# Car.net
KiCad netlist of a schematic drawn in EAGLE
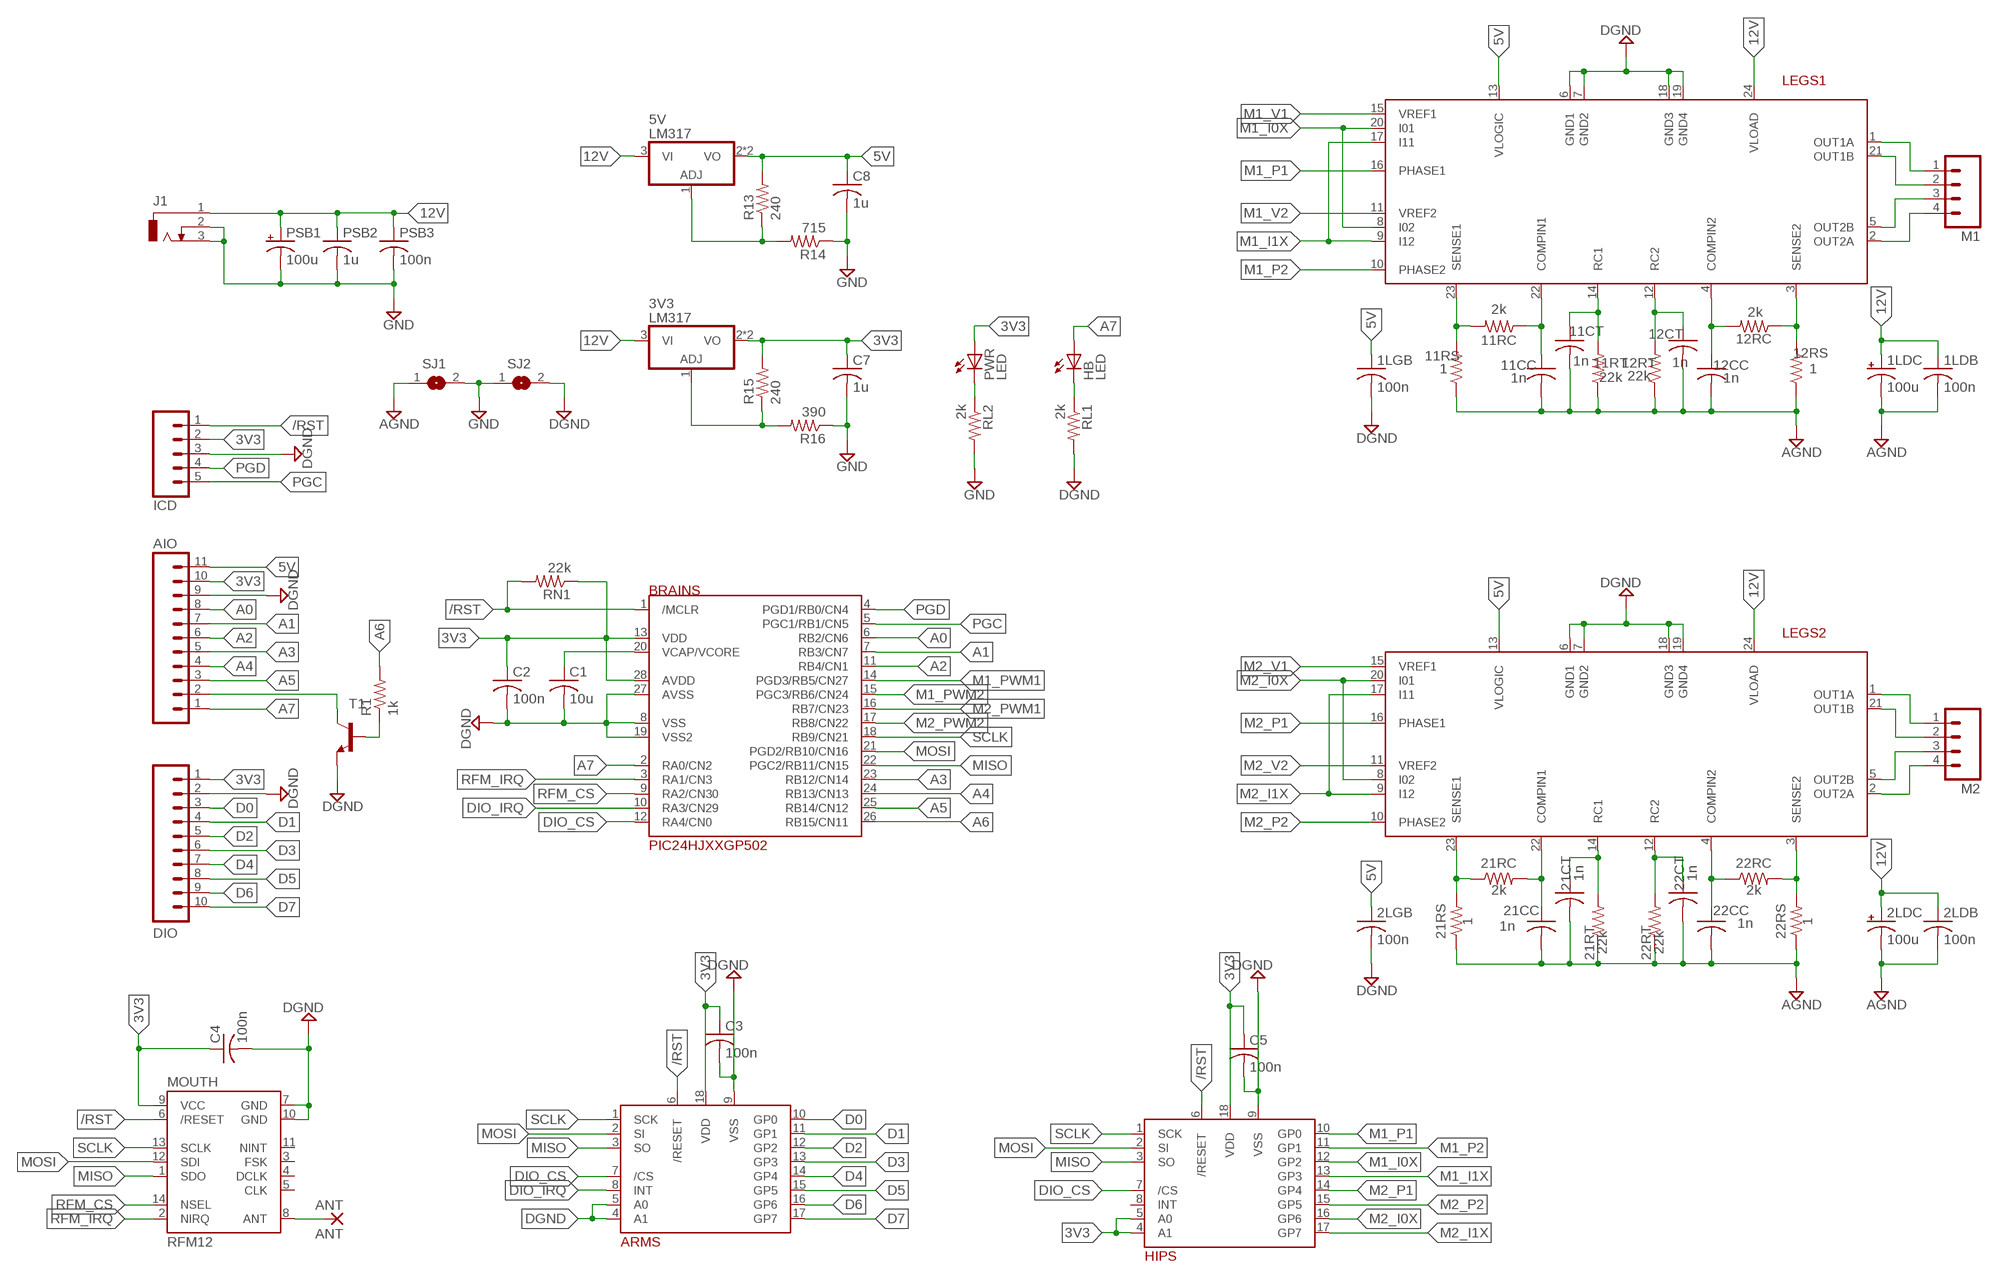
[diagram p0: schematic, sheet 1, part 1 of 2]
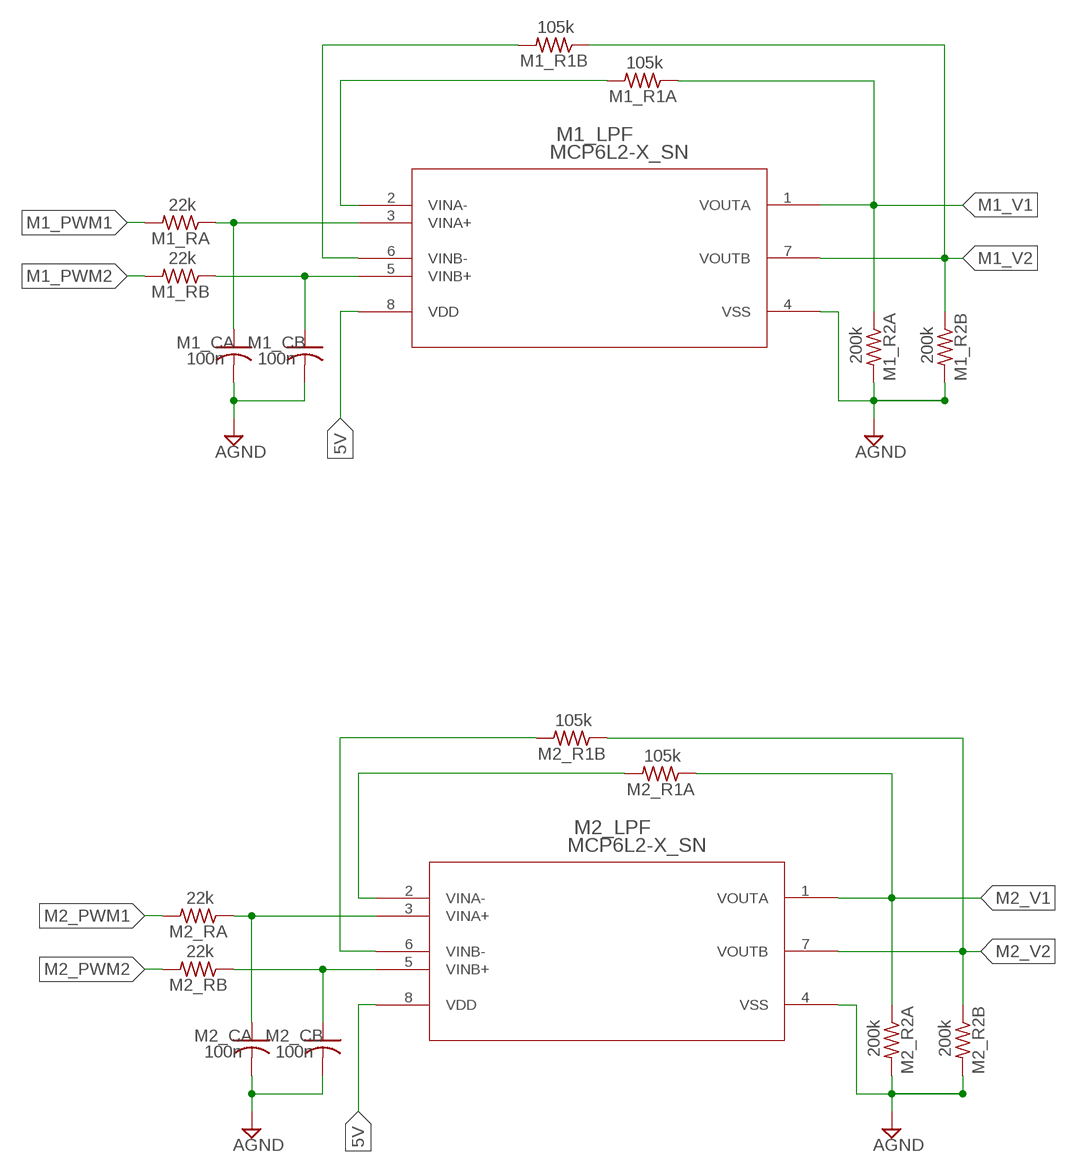
[diagram p1: schematic, sheet 1, part 2 of 2]

(export (version "E")
  (design (tool "Eeschema 10.0.6"))
  (components
    (comp (ref "1LDB")
      (value "100n")
      (footprint "eagle-import:C0805")
      (libsource (lib "eagle-import") (part "C-USC0805"))
    )
    (comp (ref "1LDC")
      (value "100u")
      (footprint "eagle-import:PANASONIC_C")
      (libsource (lib "eagle-import") (part "CAP_POLC"))
    )
    (comp (ref "1LGB")
      (value "100n")
      (footprint "eagle-import:C0805")
      (libsource (lib "eagle-import") (part "C-USC0805"))
    )
    (comp (ref "2LDB")
      (value "100n")
      (footprint "eagle-import:C0805")
      (libsource (lib "eagle-import") (part "C-USC0805"))
    )
    (comp (ref "2LDC")
      (value "100u")
      (footprint "eagle-import:PANASONIC_C")
      (libsource (lib "eagle-import") (part "CAP_POLC"))
    )
    (comp (ref "2LGB")
      (value "100n")
      (footprint "eagle-import:C0805")
      (libsource (lib "eagle-import") (part "C-USC0805"))
    )
    (comp (ref "3V3")
      (value "LM317")
      (footprint "eagle-import:SOT23")
      (libsource (lib "eagle-import") (part "LM317"))
    )
    (comp (ref "5V")
      (value "LM317")
      (footprint "eagle-import:SOT23")
      (libsource (lib "eagle-import") (part "LM317"))
    )
    (comp (ref "11CC")
      (value "1n")
      (footprint "eagle-import:C0805")
      (libsource (lib "eagle-import") (part "C-USC0805"))
    )
    (comp (ref "11CT")
      (value "1n")
      (footprint "eagle-import:C0805")
      (libsource (lib "eagle-import") (part "C-USC0805"))
    )
    (comp (ref "11RC")
      (value "2k")
      (footprint "eagle-import:R0805")
      (libsource (lib "eagle-import") (part "R-US_R0805"))
    )
    (comp (ref "11RS")
      (value "1")
      (footprint "eagle-import:R2512")
      (libsource (lib "eagle-import") (part "resistor_R-US_R2512"))
    )
    (comp (ref "11RT")
      (value "22k")
      (footprint "eagle-import:R0805")
      (libsource (lib "eagle-import") (part "R-US_R0805"))
    )
    (comp (ref "12CC")
      (value "1n")
      (footprint "eagle-import:C0805")
      (libsource (lib "eagle-import") (part "C-USC0805"))
    )
    (comp (ref "12CT")
      (value "1n")
      (footprint "eagle-import:C0805")
      (libsource (lib "eagle-import") (part "C-USC0805"))
    )
    (comp (ref "12RC")
      (value "2k")
      (footprint "eagle-import:R0805")
      (libsource (lib "eagle-import") (part "R-US_R0805"))
    )
    (comp (ref "12RS")
      (value "1")
      (footprint "eagle-import:R2512")
      (libsource (lib "eagle-import") (part "resistor_R-US_R2512"))
    )
    (comp (ref "12RT")
      (value "22k")
      (footprint "eagle-import:R0805")
      (libsource (lib "eagle-import") (part "R-US_R0805"))
    )
    (comp (ref "21CC")
      (value "1n")
      (footprint "eagle-import:C0805")
      (libsource (lib "eagle-import") (part "C-USC0805"))
    )
    (comp (ref "21CT")
      (value "1n")
      (footprint "eagle-import:C0805")
      (libsource (lib "eagle-import") (part "C-USC0805"))
    )
    (comp (ref "21RC")
      (value "2k")
      (footprint "eagle-import:R0805")
      (libsource (lib "eagle-import") (part "R-US_R0805"))
    )
    (comp (ref "21RS")
      (value "1")
      (footprint "eagle-import:R2512")
      (libsource (lib "eagle-import") (part "resistor_R-US_R2512"))
    )
    (comp (ref "21RT")
      (value "22k")
      (footprint "eagle-import:R0805")
      (libsource (lib "eagle-import") (part "R-US_R0805"))
    )
    (comp (ref "22CC")
      (value "1n")
      (footprint "eagle-import:C0805")
      (libsource (lib "eagle-import") (part "C-USC0805"))
    )
    (comp (ref "22CT")
      (value "1n")
      (footprint "eagle-import:C0805")
      (libsource (lib "eagle-import") (part "C-USC0805"))
    )
    (comp (ref "22RC")
      (value "2k")
      (footprint "eagle-import:R0805")
      (libsource (lib "eagle-import") (part "R-US_R0805"))
    )
    (comp (ref "22RS")
      (value "1")
      (footprint "eagle-import:R2512")
      (libsource (lib "eagle-import") (part "resistor_R-US_R2512"))
    )
    (comp (ref "22RT")
      (value "22k")
      (footprint "eagle-import:R0805")
      (libsource (lib "eagle-import") (part "R-US_R0805"))
    )
    (comp (ref "AIO")
      (value "M11LOCK")
      (footprint "eagle-import:1X11_LOCK")
      (libsource (lib "eagle-import") (part "M11LOCK"))
    )
    (comp (ref "ANT")
      (value "ANT")
      (footprint "eagle-import:2,15_1,0")
      (libsource (lib "eagle-import") (part "2,15/1,0"))
    )
    (comp (ref "ARMS")
      (value "MCP23S08")
      (footprint "eagle-import:SO-18W")
      (libsource (lib "eagle-import") (part "MCP23S08"))
    )
    (comp (ref "BRAINS")
      (value "PIC24HJXXGP502")
      (footprint "eagle-import:SO28W")
      (libsource (lib "eagle-import") (part "PIC24HJXXGP502"))
    )
    (comp (ref "C1")
      (value "10u")
      (footprint "eagle-import:C1206")
      (libsource (lib "eagle-import") (part "C-USC1206"))
    )
    (comp (ref "C2")
      (value "100n")
      (footprint "eagle-import:C0805")
      (libsource (lib "eagle-import") (part "C-USC0805"))
    )
    (comp (ref "C3")
      (value "100n")
      (footprint "eagle-import:C0805")
      (libsource (lib "eagle-import") (part "C-USC0805"))
    )
    (comp (ref "C4")
      (value "100n")
      (footprint "eagle-import:C0805")
      (libsource (lib "eagle-import") (part "C-USC0805"))
    )
    (comp (ref "C5")
      (value "100n")
      (footprint "eagle-import:C0805")
      (libsource (lib "eagle-import") (part "C-USC0805"))
    )
    (comp (ref "C7")
      (value "1u")
      (footprint "eagle-import:C1206")
      (libsource (lib "eagle-import") (part "C-USC1206"))
    )
    (comp (ref "C8")
      (value "1u")
      (footprint "eagle-import:C1206")
      (libsource (lib "eagle-import") (part "C-USC1206"))
    )
    (comp (ref "DIO")
      (value "M10LOCK")
      (footprint "eagle-import:1X10_LOCK")
      (libsource (lib "eagle-import") (part "M10LOCK"))
    )
    (comp (ref "HB")
      (value "LED")
      (footprint "eagle-import:CHIP-LED0805")
      (libsource (lib "eagle-import") (part "LEDCHIP-LED0805"))
    )
    (comp (ref "HIPS")
      (value "MCP23S08")
      (footprint "eagle-import:SO-18W")
      (libsource (lib "eagle-import") (part "MCP23S08"))
    )
    (comp (ref "ICD")
      (value "M05LOCK")
      (footprint "eagle-import:1X05_LOCK")
      (libsource (lib "eagle-import") (part "M05LOCK"))
    )
    (comp (ref "J1")
      (value "DCJ0303")
      (footprint "eagle-import:DCJ0303")
      (libsource (lib "eagle-import") (part "DCJ0303"))
    )
    (comp (ref "LEGS1")
      (value "MTS62C19A")
      (footprint "eagle-import:SOP24L")
      (libsource (lib "eagle-import") (part "MTS62C19A"))
    )
    (comp (ref "LEGS2")
      (value "MTS62C19A")
      (footprint "eagle-import:SOP24L")
      (libsource (lib "eagle-import") (part "MTS62C19A"))
    )
    (comp (ref "M1")
      (value "M04LOCK_LONGPADS")
      (footprint "eagle-import:1X04_LOCK_LONGPADS")
      (libsource (lib "eagle-import") (part "M04LOCK_LONGPADS"))
    )
    (comp (ref "M1_CA")
      (value "100n")
      (footprint "eagle-import:C0805")
      (libsource (lib "eagle-import") (part "C-USC0805"))
    )
    (comp (ref "M1_CB")
      (value "100n")
      (footprint "eagle-import:C0805")
      (libsource (lib "eagle-import") (part "C-USC0805"))
    )
    (comp (ref "M1_LPF")
      (value "MCP6L2-X_SN")
      (footprint "eagle-import:SOIC8-N_MC")
      (libsource (lib "eagle-import") (part "MCP6L2-X_SN"))
    )
    (comp (ref "M1_R1A")
      (value "105k")
      (footprint "eagle-import:R0805")
      (libsource (lib "eagle-import") (part "R-US_R0805"))
    )
    (comp (ref "M1_R1B")
      (value "105k")
      (footprint "eagle-import:R0805")
      (libsource (lib "eagle-import") (part "R-US_R0805"))
    )
    (comp (ref "M1_R2A")
      (value "200k")
      (footprint "eagle-import:R0805")
      (libsource (lib "eagle-import") (part "R-US_R0805"))
    )
    (comp (ref "M1_R2B")
      (value "200k")
      (footprint "eagle-import:R0805")
      (libsource (lib "eagle-import") (part "R-US_R0805"))
    )
    (comp (ref "M1_RA")
      (value "22k")
      (footprint "eagle-import:R0805")
      (libsource (lib "eagle-import") (part "R-US_R0805"))
    )
    (comp (ref "M1_RB")
      (value "22k")
      (footprint "eagle-import:R0805")
      (libsource (lib "eagle-import") (part "R-US_R0805"))
    )
    (comp (ref "M2")
      (value "M04LOCK_LONGPADS")
      (footprint "eagle-import:1X04_LOCK_LONGPADS")
      (libsource (lib "eagle-import") (part "M04LOCK_LONGPADS"))
    )
    (comp (ref "M2_CA")
      (value "100n")
      (footprint "eagle-import:C0805")
      (libsource (lib "eagle-import") (part "C-USC0805"))
    )
    (comp (ref "M2_CB")
      (value "100n")
      (footprint "eagle-import:C0805")
      (libsource (lib "eagle-import") (part "C-USC0805"))
    )
    (comp (ref "M2_LPF")
      (value "MCP6L2-X_SN")
      (footprint "eagle-import:SOIC8-N_MC")
      (libsource (lib "eagle-import") (part "MCP6L2-X_SN"))
    )
    (comp (ref "M2_R1A")
      (value "105k")
      (footprint "eagle-import:R0805")
      (libsource (lib "eagle-import") (part "R-US_R0805"))
    )
    (comp (ref "M2_R1B")
      (value "105k")
      (footprint "eagle-import:R0805")
      (libsource (lib "eagle-import") (part "R-US_R0805"))
    )
    (comp (ref "M2_R2A")
      (value "200k")
      (footprint "eagle-import:R0805")
      (libsource (lib "eagle-import") (part "R-US_R0805"))
    )
    (comp (ref "M2_R2B")
      (value "200k")
      (footprint "eagle-import:R0805")
      (libsource (lib "eagle-import") (part "R-US_R0805"))
    )
    (comp (ref "M2_RA")
      (value "22k")
      (footprint "eagle-import:R0805")
      (libsource (lib "eagle-import") (part "R-US_R0805"))
    )
    (comp (ref "M2_RB")
      (value "22k")
      (footprint "eagle-import:R0805")
      (libsource (lib "eagle-import") (part "R-US_R0805"))
    )
    (comp (ref "MOUTH")
      (value "RFM12")
      (footprint "eagle-import:RFM12-XXX-S2")
      (libsource (lib "eagle-import") (part "RFM12"))
    )
    (comp (ref "PSB1")
      (value "100u")
      (footprint "eagle-import:PANASONIC_C")
      (libsource (lib "eagle-import") (part "CAP_POLC"))
    )
    (comp (ref "PSB2")
      (value "1u")
      (footprint "eagle-import:C1206")
      (libsource (lib "eagle-import") (part "C-USC1206"))
    )
    (comp (ref "PSB3")
      (value "100n")
      (footprint "eagle-import:C0805")
      (libsource (lib "eagle-import") (part "C-USC0805"))
    )
    (comp (ref "PWR")
      (value "LED")
      (footprint "eagle-import:CHIP-LED0805")
      (libsource (lib "eagle-import") (part "LEDCHIP-LED0805"))
    )
    (comp (ref "R1")
      (value "1k")
      (footprint "eagle-import:R0805")
      (libsource (lib "eagle-import") (part "R-US_R0805"))
    )
    (comp (ref "R13")
      (value "240")
      (footprint "eagle-import:R0805")
      (libsource (lib "eagle-import") (part "R-US_R0805"))
    )
    (comp (ref "R14")
      (value "715")
      (footprint "eagle-import:R0805")
      (libsource (lib "eagle-import") (part "R-US_R0805"))
    )
    (comp (ref "R15")
      (value "240")
      (footprint "eagle-import:R0805")
      (libsource (lib "eagle-import") (part "R-US_R0805"))
    )
    (comp (ref "R16")
      (value "390")
      (footprint "eagle-import:R0805")
      (libsource (lib "eagle-import") (part "R-US_R0805"))
    )
    (comp (ref "RL1")
      (value "2k")
      (footprint "eagle-import:R0805")
      (libsource (lib "eagle-import") (part "R-US_R0805"))
    )
    (comp (ref "RL2")
      (value "2k")
      (footprint "eagle-import:R0805")
      (libsource (lib "eagle-import") (part "R-US_R0805"))
    )
    (comp (ref "RN1")
      (value "22k")
      (footprint "eagle-import:R0805")
      (libsource (lib "eagle-import") (part "R-US_R0805"))
    )
    (comp (ref "SJ1") (value "SJ") (footprint "eagle-import:SJ") (libsource (lib "eagle-import") (part "SJ")))
    (comp (ref "SJ2") (value "SJ") (footprint "eagle-import:SJ") (libsource (lib "eagle-import") (part "SJ")))
    (comp (ref "T1")
      (value "BC817-16-NPN-SOT23-BEC")
      (footprint "eagle-import:SOT23-BEC")
      (libsource (lib "eagle-import") (part "-NPN-SOT23-BECBC817-16"))
    )
  )
  (nets
    (net (code "1") (name "3V3") (class "Default")
      (node (ref "3V3") (pin "2") (pinfunction "VO_2") (pintype "passive"))
      (node (ref "3V3") (pin "4") (pinfunction "VO_4") (pintype "passive"))
      (node (ref "AIO") (pin "10") (pinfunction "10_10") (pintype "passive"))
      (node (ref "ARMS") (pin "18") (pinfunction "VDD_18") (pintype "bidirectional"))
      (node (ref "BRAINS") (pin "13") (pinfunction "VDD_13") (pintype "bidirectional"))
      (node (ref "BRAINS") (pin "28") (pinfunction "AVDD_28") (pintype "bidirectional"))
      (node (ref "C2") (pin "1") (pinfunction "1_1") (pintype "passive"))
      (node (ref "C3") (pin "1") (pinfunction "1_1") (pintype "passive"))
      (node (ref "C4") (pin "1") (pinfunction "1_1") (pintype "passive"))
      (node (ref "C5") (pin "1") (pinfunction "1_1") (pintype "passive"))
      (node (ref "C7") (pin "1") (pinfunction "1_1") (pintype "passive"))
      (node (ref "DIO") (pin "1") (pinfunction "1_1") (pintype "passive"))
      (node (ref "HIPS") (pin "18") (pinfunction "VDD_18") (pintype "bidirectional"))
      (node (ref "HIPS") (pin "4") (pinfunction "A1_4") (pintype "bidirectional"))
      (node (ref "HIPS") (pin "5") (pinfunction "A0_5") (pintype "bidirectional"))
      (node (ref "ICD") (pin "2") (pinfunction "2_2") (pintype "passive"))
      (node (ref "MOUTH") (pin "9") (pinfunction "VCC_9") (pintype "bidirectional"))
      (node (ref "PWR") (pin "A") (pinfunction "A_A") (pintype "passive"))
      (node (ref "R15") (pin "2") (pinfunction "2_2") (pintype "passive"))
      (node (ref "RN1") (pin "1") (pinfunction "1_1") (pintype "passive"))
    )
    (net (code "2") (name "5V") (class "Default")
      (node (ref "1LGB") (pin "1") (pinfunction "1_1") (pintype "passive"))
      (node (ref "2LGB") (pin "1") (pinfunction "1_1") (pintype "passive"))
      (node (ref "5V") (pin "2") (pinfunction "VO_2") (pintype "passive"))
      (node (ref "5V") (pin "4") (pinfunction "VO_4") (pintype "passive"))
      (node (ref "AIO") (pin "11") (pinfunction "11_11") (pintype "passive"))
      (node (ref "C8") (pin "1") (pinfunction "1_1") (pintype "passive"))
      (node (ref "LEGS1") (pin "13") (pinfunction "VLOGIC_13") (pintype "bidirectional"))
      (node (ref "LEGS2") (pin "13") (pinfunction "VLOGIC_13") (pintype "bidirectional"))
      (node (ref "M1_LPF") (pin "8") (pinfunction "VDD_8") (pintype "power_in"))
      (node (ref "M2_LPF") (pin "8") (pinfunction "VDD_8") (pintype "power_in"))
      (node (ref "R13") (pin "2") (pinfunction "2_2") (pintype "passive"))
    )
    (net (code "3") (name "12V") (class "Default")
      (node (ref "1LDB") (pin "1") (pinfunction "1_1") (pintype "passive"))
      (node (ref "1LDC") (pin "+") (pinfunction "+_+") (pintype "passive"))
      (node (ref "2LDB") (pin "1") (pinfunction "1_1") (pintype "passive"))
      (node (ref "2LDC") (pin "+") (pinfunction "+_+") (pintype "passive"))
      (node (ref "3V3") (pin "3") (pinfunction "VI_3") (pintype "input"))
      (node (ref "5V") (pin "3") (pinfunction "VI_3") (pintype "input"))
      (node (ref "J1") (pin "1") (pinfunction "1_1") (pintype "passive"))
      (node (ref "LEGS1") (pin "24") (pinfunction "VLOAD_24") (pintype "bidirectional"))
      (node (ref "LEGS2") (pin "24") (pinfunction "VLOAD_24") (pintype "bidirectional"))
      (node (ref "PSB1") (pin "+") (pinfunction "+_+") (pintype "passive"))
      (node (ref "PSB2") (pin "1") (pinfunction "1_1") (pintype "passive"))
      (node (ref "PSB3") (pin "1") (pinfunction "1_1") (pintype "passive"))
    )
    (net (code "4") (name "A0") (class "Default")
      (node (ref "AIO") (pin "8") (pinfunction "8_8") (pintype "passive"))
      (node (ref "BRAINS") (pin "6") (pinfunction "RB2/CN6_6") (pintype "bidirectional"))
    )
    (net (code "5") (name "A1") (class "Default")
      (node (ref "AIO") (pin "7") (pinfunction "7_7") (pintype "passive"))
      (node (ref "BRAINS") (pin "7") (pinfunction "RB3/CN7_7") (pintype "bidirectional"))
    )
    (net (code "6") (name "A2") (class "Default")
      (node (ref "AIO") (pin "6") (pinfunction "6_6") (pintype "passive"))
      (node (ref "BRAINS") (pin "11") (pinfunction "RB4/CN1_11") (pintype "bidirectional"))
    )
    (net (code "7") (name "A3") (class "Default")
      (node (ref "AIO") (pin "5") (pinfunction "5_5") (pintype "passive"))
      (node (ref "BRAINS") (pin "23") (pinfunction "RB12/CN14_23") (pintype "bidirectional"))
    )
    (net (code "8") (name "A4") (class "Default")
      (node (ref "AIO") (pin "4") (pinfunction "4_4") (pintype "passive"))
      (node (ref "BRAINS") (pin "24") (pinfunction "RB13/CN13_24") (pintype "bidirectional"))
    )
    (net (code "9") (name "A5") (class "Default")
      (node (ref "AIO") (pin "3") (pinfunction "3_3") (pintype "passive"))
      (node (ref "BRAINS") (pin "25") (pinfunction "RB14/CN12_25") (pintype "bidirectional"))
    )
    (net (code "10") (name "A6") (class "Default")
      (node (ref "BRAINS") (pin "26") (pinfunction "RB15/CN11_26") (pintype "bidirectional"))
      (node (ref "R1") (pin "2") (pinfunction "2_2") (pintype "passive"))
    )
    (net (code "11") (name "A7") (class "Default")
      (node (ref "AIO") (pin "1") (pinfunction "1_1") (pintype "passive"))
      (node (ref "BRAINS") (pin "2") (pinfunction "RA0/CN2_2") (pintype "bidirectional"))
      (node (ref "HB") (pin "A") (pinfunction "A_A") (pintype "passive"))
    )
    (net (code "12") (name "AGND") (class "Default")
      (node (ref "11CC") (pin "2") (pinfunction "2_2") (pintype "passive"))
      (node (ref "11CT") (pin "2") (pinfunction "2_2") (pintype "passive"))
      (node (ref "11RS") (pin "1") (pinfunction "1_1") (pintype "passive"))
      (node (ref "11RT") (pin "1") (pinfunction "1_1") (pintype "passive"))
      (node (ref "12CC") (pin "2") (pinfunction "2_2") (pintype "passive"))
      (node (ref "12CT") (pin "2") (pinfunction "2_2") (pintype "passive"))
      (node (ref "12RS") (pin "1") (pinfunction "1_1") (pintype "passive"))
      (node (ref "12RT") (pin "1") (pinfunction "1_1") (pintype "passive"))
      (node (ref "1LDB") (pin "2") (pinfunction "2_2") (pintype "passive"))
      (node (ref "1LDC") (pin "-") (pinfunction "-_-") (pintype "passive"))
      (node (ref "21CC") (pin "2") (pinfunction "2_2") (pintype "passive"))
      (node (ref "21CT") (pin "2") (pinfunction "2_2") (pintype "passive"))
      (node (ref "21RS") (pin "1") (pinfunction "1_1") (pintype "passive"))
      (node (ref "21RT") (pin "1") (pinfunction "1_1") (pintype "passive"))
      (node (ref "22CC") (pin "2") (pinfunction "2_2") (pintype "passive"))
      (node (ref "22CT") (pin "2") (pinfunction "2_2") (pintype "passive"))
      (node (ref "22RS") (pin "1") (pinfunction "1_1") (pintype "passive"))
      (node (ref "22RT") (pin "1") (pinfunction "1_1") (pintype "passive"))
      (node (ref "2LDB") (pin "2") (pinfunction "2_2") (pintype "passive"))
      (node (ref "2LDC") (pin "-") (pinfunction "-_-") (pintype "passive"))
      (node (ref "M1_CA") (pin "2") (pinfunction "2_2") (pintype "passive"))
      (node (ref "M1_CB") (pin "2") (pinfunction "2_2") (pintype "passive"))
      (node (ref "M1_LPF") (pin "4") (pinfunction "VSS_4") (pintype "power_in"))
      (node (ref "M1_R2A") (pin "2") (pinfunction "2_2") (pintype "passive"))
      (node (ref "M1_R2B") (pin "2") (pinfunction "2_2") (pintype "passive"))
      (node (ref "M2_CA") (pin "2") (pinfunction "2_2") (pintype "passive"))
      (node (ref "M2_CB") (pin "2") (pinfunction "2_2") (pintype "passive"))
      (node (ref "M2_LPF") (pin "4") (pinfunction "VSS_4") (pintype "power_in"))
      (node (ref "M2_R2A") (pin "2") (pinfunction "2_2") (pintype "passive"))
      (node (ref "M2_R2B") (pin "2") (pinfunction "2_2") (pintype "passive"))
      (node (ref "SJ1") (pin "1") (pinfunction "1_1") (pintype "passive"))
    )
    (net (code "13") (name "D0") (class "Default")
      (node (ref "ARMS") (pin "10") (pinfunction "GP0_10") (pintype "bidirectional"))
      (node (ref "DIO") (pin "3") (pinfunction "3_3") (pintype "passive"))
    )
    (net (code "14") (name "D1") (class "Default")
      (node (ref "ARMS") (pin "11") (pinfunction "GP1_11") (pintype "bidirectional"))
      (node (ref "DIO") (pin "4") (pinfunction "4_4") (pintype "passive"))
    )
    (net (code "15") (name "D2") (class "Default")
      (node (ref "ARMS") (pin "12") (pinfunction "GP2_12") (pintype "bidirectional"))
      (node (ref "DIO") (pin "5") (pinfunction "5_5") (pintype "passive"))
    )
    (net (code "16") (name "D3") (class "Default")
      (node (ref "ARMS") (pin "13") (pinfunction "GP3_13") (pintype "bidirectional"))
      (node (ref "DIO") (pin "6") (pinfunction "6_6") (pintype "passive"))
    )
    (net (code "17") (name "D4") (class "Default")
      (node (ref "ARMS") (pin "14") (pinfunction "GP4_14") (pintype "bidirectional"))
      (node (ref "DIO") (pin "7") (pinfunction "7_7") (pintype "passive"))
    )
    (net (code "18") (name "D5") (class "Default")
      (node (ref "ARMS") (pin "15") (pinfunction "GP5_15") (pintype "bidirectional"))
      (node (ref "DIO") (pin "8") (pinfunction "8_8") (pintype "passive"))
    )
    (net (code "19") (name "D6") (class "Default")
      (node (ref "ARMS") (pin "16") (pinfunction "GP6_16") (pintype "bidirectional"))
      (node (ref "DIO") (pin "9") (pinfunction "9_9") (pintype "passive"))
    )
    (net (code "20") (name "D7") (class "Default")
      (node (ref "ARMS") (pin "17") (pinfunction "GP7_17") (pintype "bidirectional"))
      (node (ref "DIO") (pin "10") (pinfunction "10_10") (pintype "passive"))
    )
    (net (code "21") (name "DGND") (class "Default")
      (node (ref "1LGB") (pin "2") (pinfunction "2_2") (pintype "passive"))
      (node (ref "2LGB") (pin "2") (pinfunction "2_2") (pintype "passive"))
      (node (ref "AIO") (pin "9") (pinfunction "9_9") (pintype "passive"))
      (node (ref "ARMS") (pin "4") (pinfunction "A1_4") (pintype "bidirectional"))
      (node (ref "ARMS") (pin "5") (pinfunction "A0_5") (pintype "bidirectional"))
      (node (ref "ARMS") (pin "9") (pinfunction "VSS_9") (pintype "bidirectional"))
      (node (ref "BRAINS") (pin "19") (pinfunction "VSS2_19") (pintype "bidirectional"))
      (node (ref "BRAINS") (pin "27") (pinfunction "AVSS_27") (pintype "bidirectional"))
      (node (ref "BRAINS") (pin "8") (pinfunction "VSS_8") (pintype "bidirectional"))
      (node (ref "C1") (pin "2") (pinfunction "2_2") (pintype "passive"))
      (node (ref "C2") (pin "2") (pinfunction "2_2") (pintype "passive"))
      (node (ref "C3") (pin "2") (pinfunction "2_2") (pintype "passive"))
      (node (ref "C4") (pin "2") (pinfunction "2_2") (pintype "passive"))
      (node (ref "C5") (pin "2") (pinfunction "2_2") (pintype "passive"))
      (node (ref "DIO") (pin "2") (pinfunction "2_2") (pintype "passive"))
      (node (ref "HIPS") (pin "9") (pinfunction "VSS_9") (pintype "bidirectional"))
      (node (ref "ICD") (pin "3") (pinfunction "3_3") (pintype "passive"))
      (node (ref "LEGS1") (pin "18") (pinfunction "GND3_18") (pintype "bidirectional"))
      (node (ref "LEGS1") (pin "19") (pinfunction "GND4_19") (pintype "bidirectional"))
      (node (ref "LEGS1") (pin "6") (pinfunction "GND1_6") (pintype "bidirectional"))
      (node (ref "LEGS1") (pin "7") (pinfunction "GND2_7") (pintype "bidirectional"))
      (node (ref "LEGS2") (pin "18") (pinfunction "GND3_18") (pintype "bidirectional"))
      (node (ref "LEGS2") (pin "19") (pinfunction "GND4_19") (pintype "bidirectional"))
      (node (ref "LEGS2") (pin "6") (pinfunction "GND1_6") (pintype "bidirectional"))
      (node (ref "LEGS2") (pin "7") (pinfunction "GND2_7") (pintype "bidirectional"))
      (node (ref "MOUTH") (pin "10") (pinfunction "GND_10") (pintype "bidirectional"))
      (node (ref "MOUTH") (pin "7") (pinfunction "GND_7") (pintype "bidirectional"))
      (node (ref "RL1") (pin "2") (pinfunction "2_2") (pintype "passive"))
      (node (ref "SJ2") (pin "2") (pinfunction "2_2") (pintype "passive"))
      (node (ref "T1") (pin "E") (pinfunction "E_E") (pintype "passive"))
    )
    (net (code "22") (name "DIO_CS") (class "Default")
      (node (ref "ARMS") (pin "7") (pinfunction "/CS_7") (pintype "bidirectional"))
      (node (ref "BRAINS") (pin "12") (pinfunction "RA4/CN0_12") (pintype "bidirectional"))
      (node (ref "HIPS") (pin "7") (pinfunction "/CS_7") (pintype "bidirectional"))
    )
    (net (code "23") (name "DIO_IRQ") (class "Default")
      (node (ref "ARMS") (pin "8") (pinfunction "INT_8") (pintype "bidirectional"))
      (node (ref "BRAINS") (pin "10") (pinfunction "RA3/CN29_10") (pintype "bidirectional"))
    )
    (net (code "24") (name "GND") (class "Default")
      (node (ref "C7") (pin "2") (pinfunction "2_2") (pintype "passive"))
      (node (ref "C8") (pin "2") (pinfunction "2_2") (pintype "passive"))
      (node (ref "J1") (pin "2") (pinfunction "2_2") (pintype "passive"))
      (node (ref "J1") (pin "3") (pinfunction "3_3") (pintype "passive"))
      (node (ref "PSB1") (pin "-") (pinfunction "-_-") (pintype "passive"))
      (node (ref "PSB2") (pin "2") (pinfunction "2_2") (pintype "passive"))
      (node (ref "PSB3") (pin "2") (pinfunction "2_2") (pintype "passive"))
      (node (ref "R14") (pin "1") (pinfunction "1_1") (pintype "passive"))
      (node (ref "R16") (pin "1") (pinfunction "1_1") (pintype "passive"))
      (node (ref "RL2") (pin "2") (pinfunction "2_2") (pintype "passive"))
      (node (ref "SJ1") (pin "2") (pinfunction "2_2") (pintype "passive"))
      (node (ref "SJ2") (pin "1") (pinfunction "1_1") (pintype "passive"))
    )
    (net (code "25") (name "M1_I0X") (class "Default")
      (node (ref "HIPS") (pin "12") (pinfunction "GP2_12") (pintype "bidirectional"))
      (node (ref "LEGS1") (pin "20") (pinfunction "I01_20") (pintype "bidirectional"))
      (node (ref "LEGS1") (pin "8") (pinfunction "I02_8") (pintype "bidirectional"))
    )
    (net (code "26") (name "M1_I1X") (class "Default")
      (node (ref "HIPS") (pin "13") (pinfunction "GP3_13") (pintype "bidirectional"))
      (node (ref "LEGS1") (pin "17") (pinfunction "I11_17") (pintype "bidirectional"))
      (node (ref "LEGS1") (pin "9") (pinfunction "I12_9") (pintype "bidirectional"))
    )
    (net (code "27") (name "M1_P1") (class "Default")
      (node (ref "HIPS") (pin "10") (pinfunction "GP0_10") (pintype "bidirectional"))
      (node (ref "LEGS1") (pin "16") (pinfunction "PHASE1_16") (pintype "bidirectional"))
    )
    (net (code "28") (name "M1_P2") (class "Default")
      (node (ref "HIPS") (pin "11") (pinfunction "GP1_11") (pintype "bidirectional"))
      (node (ref "LEGS1") (pin "10") (pinfunction "PHASE2_10") (pintype "bidirectional"))
    )
    (net (code "29") (name "M1_PWM1") (class "Default")
      (node (ref "BRAINS") (pin "14") (pinfunction "PGD3/RB5/CN27_14") (pintype "bidirectional"))
      (node (ref "M1_RA") (pin "2") (pinfunction "2_2") (pintype "passive"))
    )
    (net (code "30") (name "M1_PWM2") (class "Default")
      (node (ref "BRAINS") (pin "15") (pinfunction "PGC3/RB6/CN24_15") (pintype "bidirectional"))
      (node (ref "M1_RB") (pin "2") (pinfunction "2_2") (pintype "passive"))
    )
    (net (code "31") (name "M1_V1") (class "Default")
      (node (ref "LEGS1") (pin "15") (pinfunction "VREF1_15") (pintype "bidirectional"))
      (node (ref "M1_LPF") (pin "1") (pinfunction "VOUTA_1") (pintype "passive"))
      (node (ref "M1_R1A") (pin "1") (pinfunction "1_1") (pintype "passive"))
      (node (ref "M1_R2A") (pin "1") (pinfunction "1_1") (pintype "passive"))
    )
    (net (code "32") (name "M1_V2") (class "Default")
      (node (ref "LEGS1") (pin "11") (pinfunction "VREF2_11") (pintype "bidirectional"))
      (node (ref "M1_LPF") (pin "7") (pinfunction "VOUTB_7") (pintype "passive"))
      (node (ref "M1_R1B") (pin "1") (pinfunction "1_1") (pintype "passive"))
      (node (ref "M1_R2B") (pin "1") (pinfunction "1_1") (pintype "passive"))
    )
    (net (code "33") (name "M2_I0X") (class "Default")
      (node (ref "HIPS") (pin "16") (pinfunction "GP6_16") (pintype "bidirectional"))
      (node (ref "LEGS2") (pin "20") (pinfunction "I01_20") (pintype "bidirectional"))
      (node (ref "LEGS2") (pin "8") (pinfunction "I02_8") (pintype "bidirectional"))
    )
    (net (code "34") (name "M2_I1X") (class "Default")
      (node (ref "HIPS") (pin "17") (pinfunction "GP7_17") (pintype "bidirectional"))
      (node (ref "LEGS2") (pin "17") (pinfunction "I11_17") (pintype "bidirectional"))
      (node (ref "LEGS2") (pin "9") (pinfunction "I12_9") (pintype "bidirectional"))
    )
    (net (code "35") (name "M2_P1") (class "Default")
      (node (ref "HIPS") (pin "14") (pinfunction "GP4_14") (pintype "bidirectional"))
      (node (ref "LEGS2") (pin "16") (pinfunction "PHASE1_16") (pintype "bidirectional"))
    )
    (net (code "36") (name "M2_P2") (class "Default")
      (node (ref "HIPS") (pin "15") (pinfunction "GP5_15") (pintype "bidirectional"))
      (node (ref "LEGS2") (pin "10") (pinfunction "PHASE2_10") (pintype "bidirectional"))
    )
    (net (code "37") (name "M2_PWM1") (class "Default")
      (node (ref "BRAINS") (pin "16") (pinfunction "RB7/CN23_16") (pintype "bidirectional"))
      (node (ref "M2_RA") (pin "2") (pinfunction "2_2") (pintype "passive"))
    )
    (net (code "38") (name "M2_PWM2") (class "Default")
      (node (ref "BRAINS") (pin "17") (pinfunction "RB8/CN22_17") (pintype "bidirectional"))
      (node (ref "M2_RB") (pin "2") (pinfunction "2_2") (pintype "passive"))
    )
    (net (code "39") (name "M2_V1") (class "Default")
      (node (ref "LEGS2") (pin "15") (pinfunction "VREF1_15") (pintype "bidirectional"))
      (node (ref "M2_LPF") (pin "1") (pinfunction "VOUTA_1") (pintype "passive"))
      (node (ref "M2_R1A") (pin "1") (pinfunction "1_1") (pintype "passive"))
      (node (ref "M2_R2A") (pin "1") (pinfunction "1_1") (pintype "passive"))
    )
    (net (code "40") (name "M2_V2") (class "Default")
      (node (ref "LEGS2") (pin "11") (pinfunction "VREF2_11") (pintype "bidirectional"))
      (node (ref "M2_LPF") (pin "7") (pinfunction "VOUTB_7") (pintype "passive"))
      (node (ref "M2_R1B") (pin "1") (pinfunction "1_1") (pintype "passive"))
      (node (ref "M2_R2B") (pin "1") (pinfunction "1_1") (pintype "passive"))
    )
    (net (code "41") (name "MISO") (class "Default")
      (node (ref "ARMS") (pin "3") (pinfunction "SO_3") (pintype "bidirectional"))
      (node (ref "BRAINS") (pin "22") (pinfunction "PGC2/RB11/CN15_22") (pintype "bidirectional"))
      (node (ref "HIPS") (pin "3") (pinfunction "SO_3") (pintype "bidirectional"))
      (node (ref "MOUTH") (pin "1") (pinfunction "SDO_1") (pintype "output"))
    )
    (net (code "42") (name "MOSI") (class "Default")
      (node (ref "ARMS") (pin "2") (pinfunction "SI_2") (pintype "bidirectional"))
      (node (ref "BRAINS") (pin "21") (pinfunction "PGD2/RB10/CN16_21") (pintype "bidirectional"))
      (node (ref "HIPS") (pin "2") (pinfunction "SI_2") (pintype "bidirectional"))
      (node (ref "MOUTH") (pin "12") (pinfunction "SDI_12") (pintype "input"))
    )
    (net (code "43") (name "Net-(3V3-ADJ)") (class "Default")
      (node (ref "3V3") (pin "1") (pinfunction "ADJ_1") (pintype "input"))
      (node (ref "R15") (pin "1") (pinfunction "1_1") (pintype "passive"))
      (node (ref "R16") (pin "2") (pinfunction "2_2") (pintype "passive"))
    )
    (net (code "44") (name "Net-(5V-ADJ)") (class "Default")
      (node (ref "5V") (pin "1") (pinfunction "ADJ_1") (pintype "input"))
      (node (ref "R13") (pin "1") (pinfunction "1_1") (pintype "passive"))
      (node (ref "R14") (pin "2") (pinfunction "2_2") (pintype "passive"))
    )
    (net (code "45") (name "Net-(AIO-Pad2)") (class "Default")
      (node (ref "AIO") (pin "2") (pinfunction "2_2") (pintype "passive"))
      (node (ref "T1") (pin "C") (pinfunction "C_C") (pintype "passive"))
    )
    (net (code "46") (name "Net-(ANT-P)") (class "Default")
      (node (ref "ANT") (pin "1") (pinfunction "P_1") (pintype "passive"))
      (node (ref "MOUTH") (pin "8") (pinfunction "ANT_8") (pintype "bidirectional"))
    )
    (net (code "47") (name "Net-(BRAINS-VCAP{slash}VCORE)") (class "Default")
      (node (ref "BRAINS") (pin "20") (pinfunction "VCAP/VCORE_20") (pintype "bidirectional"))
      (node (ref "C1") (pin "1") (pinfunction "1_1") (pintype "passive"))
    )
    (net (code "48") (name "Net-(HB-PadC)") (class "Default")
      (node (ref "HB") (pin "C") (pinfunction "C_C") (pintype "passive"))
      (node (ref "RL1") (pin "1") (pinfunction "1_1") (pintype "passive"))
    )
    (net (code "49") (name "Net-(LEGS1-COMPIN1)") (class "Default")
      (node (ref "11CC") (pin "1") (pinfunction "1_1") (pintype "passive"))
      (node (ref "11RC") (pin "1") (pinfunction "1_1") (pintype "passive"))
      (node (ref "LEGS1") (pin "22") (pinfunction "COMPIN1_22") (pintype "bidirectional"))
    )
    (net (code "50") (name "Net-(LEGS1-COMPIN2)") (class "Default")
      (node (ref "12CC") (pin "1") (pinfunction "1_1") (pintype "passive"))
      (node (ref "12RC") (pin "2") (pinfunction "2_2") (pintype "passive"))
      (node (ref "LEGS1") (pin "4") (pinfunction "COMPIN2_4") (pintype "bidirectional"))
    )
    (net (code "51") (name "Net-(LEGS1-OUT1A)") (class "Default")
      (node (ref "LEGS1") (pin "1") (pinfunction "OUT1A_1") (pintype "bidirectional"))
      (node (ref "M1") (pin "1") (pinfunction "1_1") (pintype "passive"))
    )
    (net (code "52") (name "Net-(LEGS1-OUT1B)") (class "Default")
      (node (ref "LEGS1") (pin "21") (pinfunction "OUT1B_21") (pintype "bidirectional"))
      (node (ref "M1") (pin "2") (pinfunction "2_2") (pintype "passive"))
    )
    (net (code "53") (name "Net-(LEGS1-OUT2A)") (class "Default")
      (node (ref "LEGS1") (pin "2") (pinfunction "OUT2A_2") (pintype "bidirectional"))
      (node (ref "M1") (pin "4") (pinfunction "4_4") (pintype "passive"))
    )
    (net (code "54") (name "Net-(LEGS1-OUT2B)") (class "Default")
      (node (ref "LEGS1") (pin "5") (pinfunction "OUT2B_5") (pintype "bidirectional"))
      (node (ref "M1") (pin "3") (pinfunction "3_3") (pintype "passive"))
    )
    (net (code "55") (name "Net-(LEGS1-RC1)") (class "Default")
      (node (ref "11CT") (pin "1") (pinfunction "1_1") (pintype "passive"))
      (node (ref "11RT") (pin "2") (pinfunction "2_2") (pintype "passive"))
      (node (ref "LEGS1") (pin "14") (pinfunction "RC1_14") (pintype "bidirectional"))
    )
    (net (code "56") (name "Net-(LEGS1-RC2)") (class "Default")
      (node (ref "12CT") (pin "1") (pinfunction "1_1") (pintype "passive"))
      (node (ref "12RT") (pin "2") (pinfunction "2_2") (pintype "passive"))
      (node (ref "LEGS1") (pin "12") (pinfunction "RC2_12") (pintype "bidirectional"))
    )
    (net (code "57") (name "Net-(LEGS1-SENSE1)") (class "Default")
      (node (ref "11RC") (pin "2") (pinfunction "2_2") (pintype "passive"))
      (node (ref "11RS") (pin "2") (pinfunction "2_2") (pintype "passive"))
      (node (ref "LEGS1") (pin "23") (pinfunction "SENSE1_23") (pintype "bidirectional"))
    )
    (net (code "58") (name "Net-(LEGS1-SENSE2)") (class "Default")
      (node (ref "12RC") (pin "1") (pinfunction "1_1") (pintype "passive"))
      (node (ref "12RS") (pin "2") (pinfunction "2_2") (pintype "passive"))
      (node (ref "LEGS1") (pin "3") (pinfunction "SENSE2_3") (pintype "bidirectional"))
    )
    (net (code "59") (name "Net-(LEGS2-COMPIN1)") (class "Default")
      (node (ref "21CC") (pin "1") (pinfunction "1_1") (pintype "passive"))
      (node (ref "21RC") (pin "2") (pinfunction "2_2") (pintype "passive"))
      (node (ref "LEGS2") (pin "22") (pinfunction "COMPIN1_22") (pintype "bidirectional"))
    )
    (net (code "60") (name "Net-(LEGS2-COMPIN2)") (class "Default")
      (node (ref "22CC") (pin "1") (pinfunction "1_1") (pintype "passive"))
      (node (ref "22RC") (pin "1") (pinfunction "1_1") (pintype "passive"))
      (node (ref "LEGS2") (pin "4") (pinfunction "COMPIN2_4") (pintype "bidirectional"))
    )
    (net (code "61") (name "Net-(LEGS2-OUT1A)") (class "Default")
      (node (ref "LEGS2") (pin "1") (pinfunction "OUT1A_1") (pintype "bidirectional"))
      (node (ref "M2") (pin "1") (pinfunction "1_1") (pintype "passive"))
    )
    (net (code "62") (name "Net-(LEGS2-OUT1B)") (class "Default")
      (node (ref "LEGS2") (pin "21") (pinfunction "OUT1B_21") (pintype "bidirectional"))
      (node (ref "M2") (pin "2") (pinfunction "2_2") (pintype "passive"))
    )
    (net (code "63") (name "Net-(LEGS2-OUT2A)") (class "Default")
      (node (ref "LEGS2") (pin "2") (pinfunction "OUT2A_2") (pintype "bidirectional"))
      (node (ref "M2") (pin "4") (pinfunction "4_4") (pintype "passive"))
    )
    (net (code "64") (name "Net-(LEGS2-OUT2B)") (class "Default")
      (node (ref "LEGS2") (pin "5") (pinfunction "OUT2B_5") (pintype "bidirectional"))
      (node (ref "M2") (pin "3") (pinfunction "3_3") (pintype "passive"))
    )
    (net (code "65") (name "Net-(LEGS2-RC1)") (class "Default")
      (node (ref "21CT") (pin "1") (pinfunction "1_1") (pintype "passive"))
      (node (ref "21RT") (pin "2") (pinfunction "2_2") (pintype "passive"))
      (node (ref "LEGS2") (pin "14") (pinfunction "RC1_14") (pintype "bidirectional"))
    )
    (net (code "66") (name "Net-(LEGS2-RC2)") (class "Default")
      (node (ref "22CT") (pin "1") (pinfunction "1_1") (pintype "passive"))
      (node (ref "22RT") (pin "2") (pinfunction "2_2") (pintype "passive"))
      (node (ref "LEGS2") (pin "12") (pinfunction "RC2_12") (pintype "bidirectional"))
    )
    (net (code "67") (name "Net-(LEGS2-SENSE1)") (class "Default")
      (node (ref "21RC") (pin "1") (pinfunction "1_1") (pintype "passive"))
      (node (ref "21RS") (pin "2") (pinfunction "2_2") (pintype "passive"))
      (node (ref "LEGS2") (pin "23") (pinfunction "SENSE1_23") (pintype "bidirectional"))
    )
    (net (code "68") (name "Net-(LEGS2-SENSE2)") (class "Default")
      (node (ref "22RC") (pin "2") (pinfunction "2_2") (pintype "passive"))
      (node (ref "22RS") (pin "2") (pinfunction "2_2") (pintype "passive"))
      (node (ref "LEGS2") (pin "3") (pinfunction "SENSE2_3") (pintype "bidirectional"))
    )
    (net (code "69") (name "Net-(M1_LPF-VINA+)") (class "Default")
      (node (ref "M1_CA") (pin "1") (pinfunction "1_1") (pintype "passive"))
      (node (ref "M1_LPF") (pin "3") (pinfunction "VINA+_3") (pintype "passive"))
      (node (ref "M1_RA") (pin "1") (pinfunction "1_1") (pintype "passive"))
    )
    (net (code "70") (name "Net-(M1_LPF-VINA-)") (class "Default")
      (node (ref "M1_LPF") (pin "2") (pinfunction "VINA-_2") (pintype "passive"))
      (node (ref "M1_R1A") (pin "2") (pinfunction "2_2") (pintype "passive"))
    )
    (net (code "71") (name "Net-(M1_LPF-VINB+)") (class "Default")
      (node (ref "M1_CB") (pin "1") (pinfunction "1_1") (pintype "passive"))
      (node (ref "M1_LPF") (pin "5") (pinfunction "VINB+_5") (pintype "passive"))
      (node (ref "M1_RB") (pin "1") (pinfunction "1_1") (pintype "passive"))
    )
    (net (code "72") (name "Net-(M1_LPF-VINB-)") (class "Default")
      (node (ref "M1_LPF") (pin "6") (pinfunction "VINB-_6") (pintype "passive"))
      (node (ref "M1_R1B") (pin "2") (pinfunction "2_2") (pintype "passive"))
    )
    (net (code "73") (name "Net-(M2_LPF-VINA+)") (class "Default")
      (node (ref "M2_CA") (pin "1") (pinfunction "1_1") (pintype "passive"))
      (node (ref "M2_LPF") (pin "3") (pinfunction "VINA+_3") (pintype "passive"))
      (node (ref "M2_RA") (pin "1") (pinfunction "1_1") (pintype "passive"))
    )
    (net (code "74") (name "Net-(M2_LPF-VINA-)") (class "Default")
      (node (ref "M2_LPF") (pin "2") (pinfunction "VINA-_2") (pintype "passive"))
      (node (ref "M2_R1A") (pin "2") (pinfunction "2_2") (pintype "passive"))
    )
    (net (code "75") (name "Net-(M2_LPF-VINB+)") (class "Default")
      (node (ref "M2_CB") (pin "1") (pinfunction "1_1") (pintype "passive"))
      (node (ref "M2_LPF") (pin "5") (pinfunction "VINB+_5") (pintype "passive"))
      (node (ref "M2_RB") (pin "1") (pinfunction "1_1") (pintype "passive"))
    )
    (net (code "76") (name "Net-(M2_LPF-VINB-)") (class "Default")
      (node (ref "M2_LPF") (pin "6") (pinfunction "VINB-_6") (pintype "passive"))
      (node (ref "M2_R1B") (pin "2") (pinfunction "2_2") (pintype "passive"))
    )
    (net (code "77") (name "Net-(PWR-PadC)") (class "Default")
      (node (ref "PWR") (pin "C") (pinfunction "C_C") (pintype "passive"))
      (node (ref "RL2") (pin "1") (pinfunction "1_1") (pintype "passive"))
    )
    (net (code "78") (name "Net-(R1-Pad1)") (class "Default")
      (node (ref "R1") (pin "1") (pinfunction "1_1") (pintype "passive"))
      (node (ref "T1") (pin "B") (pinfunction "B_B") (pintype "passive"))
    )
    (net (code "79") (name "PGC") (class "Default")
      (node (ref "BRAINS") (pin "5") (pinfunction "PGC1/RB1/CN5_5") (pintype "bidirectional"))
      (node (ref "ICD") (pin "5") (pinfunction "5_5") (pintype "passive"))
    )
    (net (code "80") (name "PGD") (class "Default")
      (node (ref "BRAINS") (pin "4") (pinfunction "PGD1/RB0/CN4_4") (pintype "bidirectional"))
      (node (ref "ICD") (pin "4") (pinfunction "4_4") (pintype "passive"))
    )
    (net (code "81") (name "RFM_CS") (class "Default")
      (node (ref "BRAINS") (pin "9") (pinfunction "RA2/CN30_9") (pintype "bidirectional"))
      (node (ref "MOUTH") (pin "14") (pinfunction "NSEL_14") (pintype "input"))
    )
    (net (code "82") (name "RFM_IRQ") (class "Default")
      (node (ref "BRAINS") (pin "3") (pinfunction "RA1/CN3_3") (pintype "bidirectional"))
      (node (ref "MOUTH") (pin "2") (pinfunction "NIRQ_2") (pintype "output"))
    )
    (net (code "83") (name "SCLK") (class "Default")
      (node (ref "ARMS") (pin "1") (pinfunction "SCK_1") (pintype "bidirectional"))
      (node (ref "BRAINS") (pin "18") (pinfunction "RB9/CN21_18") (pintype "bidirectional"))
      (node (ref "HIPS") (pin "1") (pinfunction "SCK_1") (pintype "bidirectional"))
      (node (ref "MOUTH") (pin "13") (pinfunction "SCLK_13") (pintype "input"))
    )
    (net (code "84") (name "unconnected-(HIPS-INT-Pad8)") (class "Default")
      (node (ref "HIPS") (pin "8") (pinfunction "INT_8") (pintype "bidirectional"))
    )
    (net (code "85") (name "unconnected-(MOUTH-CLK-Pad5)") (class "Default")
      (node (ref "MOUTH") (pin "5") (pinfunction "CLK_5") (pintype "bidirectional"))
    )
    (net (code "86") (name "unconnected-(MOUTH-DCLK-Pad4)") (class "Default")
      (node (ref "MOUTH") (pin "4") (pinfunction "DCLK_4") (pintype "bidirectional"))
    )
    (net (code "87") (name "unconnected-(MOUTH-FSK-Pad3)") (class "Default")
      (node (ref "MOUTH") (pin "3") (pinfunction "FSK_3") (pintype "bidirectional"))
    )
    (net (code "88") (name "unconnected-(MOUTH-NINT-Pad11)") (class "Default")
      (node (ref "MOUTH") (pin "11") (pinfunction "NINT_11") (pintype "bidirectional"))
    )
    (net (code "89") (name "{slash}RST") (class "Default")
      (node (ref "ARMS") (pin "6") (pinfunction "/RESET_6") (pintype "bidirectional"))
      (node (ref "BRAINS") (pin "1") (pinfunction "/MCLR_1") (pintype "bidirectional"))
      (node (ref "HIPS") (pin "6") (pinfunction "/RESET_6") (pintype "bidirectional"))
      (node (ref "ICD") (pin "1") (pinfunction "1_1") (pintype "passive"))
      (node (ref "MOUTH") (pin "6") (pinfunction "/RESET_6") (pintype "bidirectional"))
      (node (ref "RN1") (pin "2") (pinfunction "2_2") (pintype "passive"))
    )
  )
)
